# arrayboard_r0.net
KiCad netlist of a schematic drawn in EAGLE
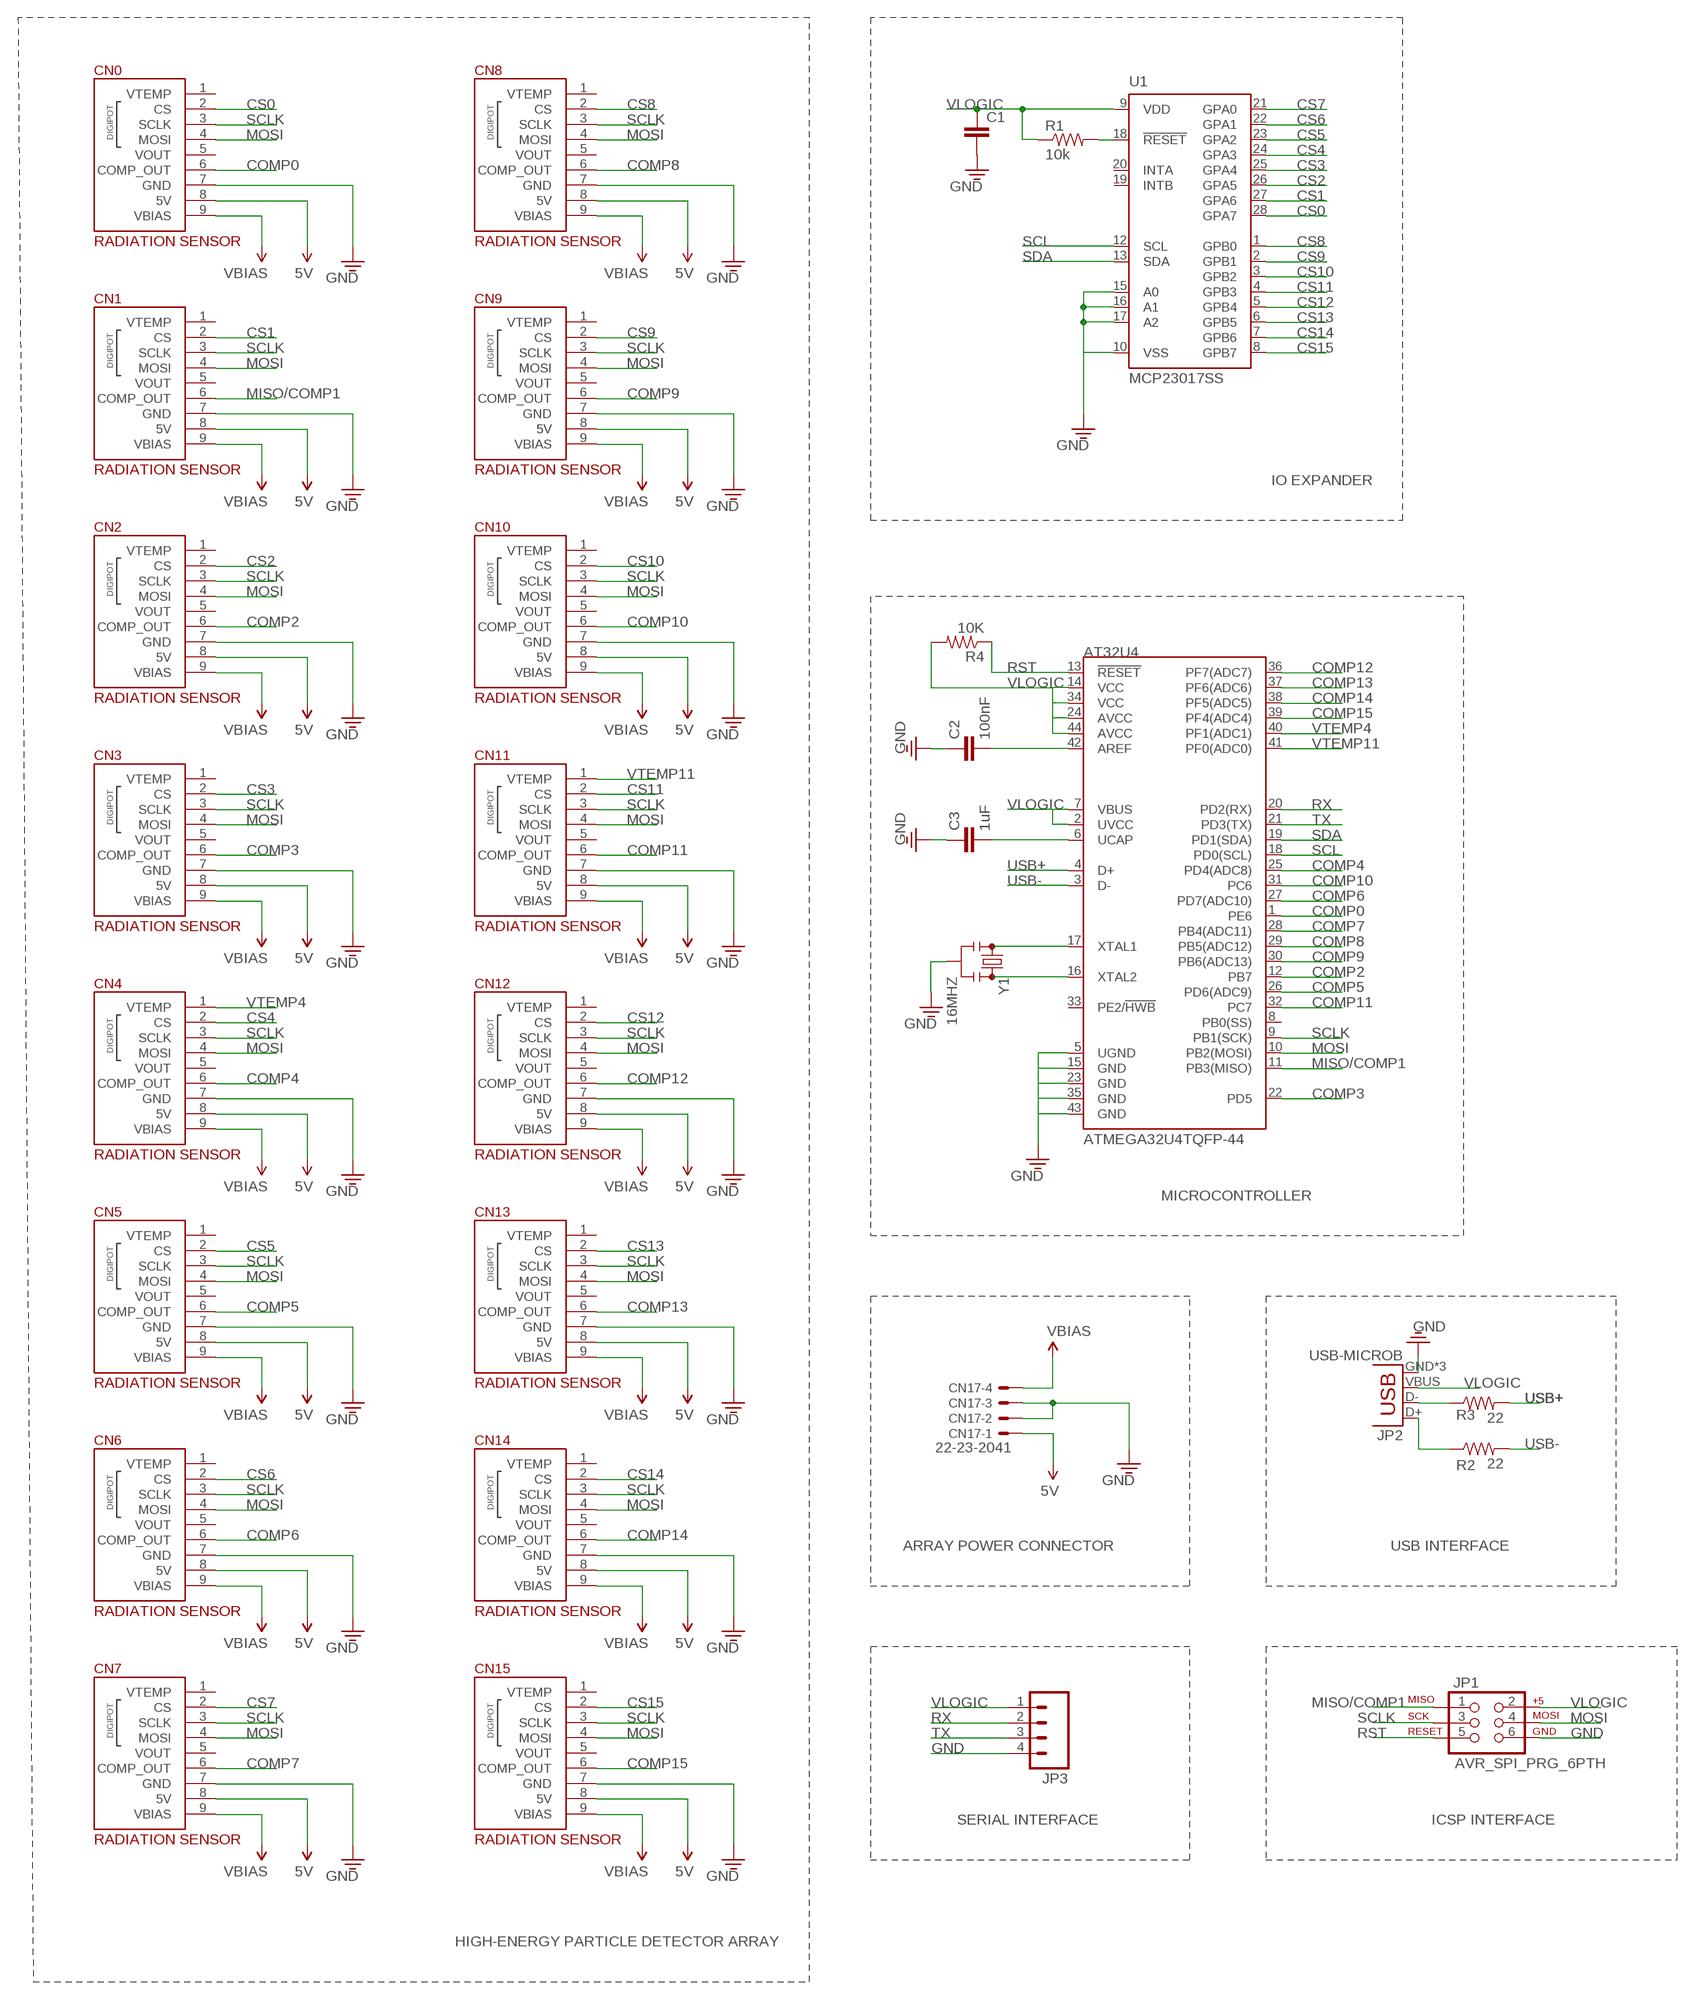
[diagram p0: schematic, sheet 1]

(export (version "E")
  (design (tool "Eeschema 10.0.6"))
  (components
    (comp (ref "AT32U4")
      (value "ATMEGA32U4TQFP-44")
      (footprint "eagle-import:TQFP44")
      (libsource (lib "eagle-import") (part "ATMEGA32U4TQFP-44"))
    )
    (comp (ref "C1")
      (value "CAP0603")
      (footprint "eagle-import:0603")
      (libsource (lib "eagle-import") (part "CAP0603"))
    )
    (comp (ref "C2")
      (value "100nF")
      (footprint "eagle-import:0805")
      (libsource (lib "eagle-import") (part "CAP0805"))
    )
    (comp (ref "C3")
      (value "1uF")
      (footprint "eagle-import:0805")
      (libsource (lib "eagle-import") (part "CAP0805"))
    )
    (comp (ref "CN0")
      (value "RADIATION-SENSOR-REV1")
      (footprint "eagle-import:RADIATION-SENSOR-REV1")
      (libsource (lib "eagle-import") (part "RADIATION-SENSOR-REV1"))
    )
    (comp (ref "CN1")
      (value "RADIATION-SENSOR-REV1")
      (footprint "eagle-import:RADIATION-SENSOR-REV1")
      (libsource (lib "eagle-import") (part "RADIATION-SENSOR-REV1"))
    )
    (comp (ref "CN2")
      (value "RADIATION-SENSOR-REV1")
      (footprint "eagle-import:RADIATION-SENSOR-REV1")
      (libsource (lib "eagle-import") (part "RADIATION-SENSOR-REV1"))
    )
    (comp (ref "CN3")
      (value "RADIATION-SENSOR-REV1")
      (footprint "eagle-import:RADIATION-SENSOR-REV1")
      (libsource (lib "eagle-import") (part "RADIATION-SENSOR-REV1"))
    )
    (comp (ref "CN4")
      (value "RADIATION-SENSOR-REV1")
      (footprint "eagle-import:RADIATION-SENSOR-REV1")
      (libsource (lib "eagle-import") (part "RADIATION-SENSOR-REV1"))
    )
    (comp (ref "CN5")
      (value "RADIATION-SENSOR-REV1")
      (footprint "eagle-import:RADIATION-SENSOR-REV1")
      (libsource (lib "eagle-import") (part "RADIATION-SENSOR-REV1"))
    )
    (comp (ref "CN6")
      (value "RADIATION-SENSOR-REV1")
      (footprint "eagle-import:RADIATION-SENSOR-REV1")
      (libsource (lib "eagle-import") (part "RADIATION-SENSOR-REV1"))
    )
    (comp (ref "CN7")
      (value "RADIATION-SENSOR-REV1")
      (footprint "eagle-import:RADIATION-SENSOR-REV1")
      (libsource (lib "eagle-import") (part "RADIATION-SENSOR-REV1"))
    )
    (comp (ref "CN8")
      (value "RADIATION-SENSOR-REV1")
      (footprint "eagle-import:RADIATION-SENSOR-REV1")
      (libsource (lib "eagle-import") (part "RADIATION-SENSOR-REV1"))
    )
    (comp (ref "CN9")
      (value "RADIATION-SENSOR-REV1")
      (footprint "eagle-import:RADIATION-SENSOR-REV1")
      (libsource (lib "eagle-import") (part "RADIATION-SENSOR-REV1"))
    )
    (comp (ref "CN10")
      (value "RADIATION-SENSOR-REV1")
      (footprint "eagle-import:RADIATION-SENSOR-REV1")
      (libsource (lib "eagle-import") (part "RADIATION-SENSOR-REV1"))
    )
    (comp (ref "CN11")
      (value "RADIATION-SENSOR-REV1")
      (footprint "eagle-import:RADIATION-SENSOR-REV1")
      (libsource (lib "eagle-import") (part "RADIATION-SENSOR-REV1"))
    )
    (comp (ref "CN12")
      (value "RADIATION-SENSOR-REV1")
      (footprint "eagle-import:RADIATION-SENSOR-REV1")
      (libsource (lib "eagle-import") (part "RADIATION-SENSOR-REV1"))
    )
    (comp (ref "CN13")
      (value "RADIATION-SENSOR-REV1")
      (footprint "eagle-import:RADIATION-SENSOR-REV1")
      (libsource (lib "eagle-import") (part "RADIATION-SENSOR-REV1"))
    )
    (comp (ref "CN14")
      (value "RADIATION-SENSOR-REV1")
      (footprint "eagle-import:RADIATION-SENSOR-REV1")
      (libsource (lib "eagle-import") (part "RADIATION-SENSOR-REV1"))
    )
    (comp (ref "CN15")
      (value "RADIATION-SENSOR-REV1")
      (footprint "eagle-import:RADIATION-SENSOR-REV1")
      (libsource (lib "eagle-import") (part "RADIATION-SENSOR-REV1"))
    )
    (comp (ref "CN17")
      (value "22-23-2041")
      (footprint "eagle-import:22-23-2041")
      (fields (field (name "MF") "MOLEX"))
      (libsource (lib "eagle-import") (part "22-23-2041"))
    )
    (comp (ref "JP1")
      (value "AVR_SPI_PRG_6PTH")
      (footprint "eagle-import:2X3")
      (libsource (lib "eagle-import") (part "AVR_SPI_PRG_6PTH"))
    )
    (comp (ref "JP2")
      (value "USB-MICROB")
      (footprint "eagle-import:USB-MICROB")
      (libsource (lib "eagle-import") (part "USB-MICROB"))
    )
    (comp (ref "JP3")
      (value "M04POLAR")
      (footprint "eagle-import:MOLEX-1X4")
      (libsource (lib "eagle-import") (part "M04POLAR"))
    )
    (comp (ref "R1")
      (value "10k")
      (footprint "eagle-import:0603")
      (libsource (lib "eagle-import") (part "RESISTOR0603"))
    )
    (comp (ref "R2")
      (value "22")
      (footprint "eagle-import:0805")
      (libsource (lib "eagle-import") (part "RESISTOR0805-RES"))
    )
    (comp (ref "R3")
      (value "22")
      (footprint "eagle-import:0805")
      (libsource (lib "eagle-import") (part "RESISTOR0805-RES"))
    )
    (comp (ref "R4")
      (value "10K")
      (footprint "eagle-import:0805")
      (libsource (lib "eagle-import") (part "RESISTOR0805-RES"))
    )
    (comp (ref "U1")
      (value "MCP23017SS")
      (footprint "eagle-import:SSOP28")
      (libsource (lib "eagle-import") (part "MCP23017SS"))
    )
    (comp (ref "Y1")
      (value "16MHZ")
      (footprint "eagle-import:RESONATOR-SMD")
      (libsource (lib "eagle-import") (part "RESONATOR16MHZ"))
    )
  )
  (nets
    (net (code "1") (name "/COMP0") (class "Default")
      (node (ref "AT32U4") (pin "1") (pinfunction "PE6_1") (pintype "bidirectional"))
      (node (ref "CN0") (pin "6") (pinfunction "COMP_OUT_6") (pintype "bidirectional"))
    )
    (net (code "2") (name "/COMP2") (class "Default")
      (node (ref "AT32U4") (pin "12") (pinfunction "PB7_12") (pintype "bidirectional"))
      (node (ref "CN2") (pin "6") (pinfunction "COMP_OUT_6") (pintype "bidirectional"))
    )
    (net (code "3") (name "/COMP3") (class "Default")
      (node (ref "AT32U4") (pin "22") (pinfunction "PD5_22") (pintype "bidirectional"))
      (node (ref "CN3") (pin "6") (pinfunction "COMP_OUT_6") (pintype "bidirectional"))
    )
    (net (code "4") (name "/COMP4") (class "Default")
      (node (ref "AT32U4") (pin "25") (pinfunction "PD4(ADC8)_25") (pintype "bidirectional"))
      (node (ref "CN4") (pin "6") (pinfunction "COMP_OUT_6") (pintype "bidirectional"))
    )
    (net (code "5") (name "/COMP5") (class "Default")
      (node (ref "AT32U4") (pin "26") (pinfunction "PD6(ADC9)_26") (pintype "bidirectional"))
      (node (ref "CN5") (pin "6") (pinfunction "COMP_OUT_6") (pintype "bidirectional"))
    )
    (net (code "6") (name "/COMP6") (class "Default")
      (node (ref "AT32U4") (pin "27") (pinfunction "PD7(ADC10)_27") (pintype "bidirectional"))
      (node (ref "CN6") (pin "6") (pinfunction "COMP_OUT_6") (pintype "bidirectional"))
    )
    (net (code "7") (name "/COMP7") (class "Default")
      (node (ref "AT32U4") (pin "28") (pinfunction "PB4(ADC11)_28") (pintype "bidirectional"))
      (node (ref "CN7") (pin "6") (pinfunction "COMP_OUT_6") (pintype "bidirectional"))
    )
    (net (code "8") (name "/COMP8") (class "Default")
      (node (ref "AT32U4") (pin "29") (pinfunction "PB5(ADC12)_29") (pintype "bidirectional"))
      (node (ref "CN8") (pin "6") (pinfunction "COMP_OUT_6") (pintype "bidirectional"))
    )
    (net (code "9") (name "/COMP9") (class "Default")
      (node (ref "AT32U4") (pin "30") (pinfunction "PB6(ADC13)_30") (pintype "bidirectional"))
      (node (ref "CN9") (pin "6") (pinfunction "COMP_OUT_6") (pintype "bidirectional"))
    )
    (net (code "10") (name "/COMP10") (class "Default")
      (node (ref "AT32U4") (pin "31") (pinfunction "PC6_31") (pintype "bidirectional"))
      (node (ref "CN10") (pin "6") (pinfunction "COMP_OUT_6") (pintype "bidirectional"))
    )
    (net (code "11") (name "/COMP11") (class "Default")
      (node (ref "AT32U4") (pin "32") (pinfunction "PC7_32") (pintype "bidirectional"))
      (node (ref "CN11") (pin "6") (pinfunction "COMP_OUT_6") (pintype "bidirectional"))
    )
    (net (code "12") (name "/COMP12") (class "Default")
      (node (ref "AT32U4") (pin "36") (pinfunction "PF7(ADC7)_36") (pintype "bidirectional"))
      (node (ref "CN12") (pin "6") (pinfunction "COMP_OUT_6") (pintype "bidirectional"))
    )
    (net (code "13") (name "/COMP13") (class "Default")
      (node (ref "AT32U4") (pin "37") (pinfunction "PF6(ADC6)_37") (pintype "bidirectional"))
      (node (ref "CN13") (pin "6") (pinfunction "COMP_OUT_6") (pintype "bidirectional"))
    )
    (net (code "14") (name "/COMP14") (class "Default")
      (node (ref "AT32U4") (pin "38") (pinfunction "PF5(ADC5)_38") (pintype "bidirectional"))
      (node (ref "CN14") (pin "6") (pinfunction "COMP_OUT_6") (pintype "bidirectional"))
    )
    (net (code "15") (name "/COMP15") (class "Default")
      (node (ref "AT32U4") (pin "39") (pinfunction "PF4(ADC4)_39") (pintype "bidirectional"))
      (node (ref "CN15") (pin "6") (pinfunction "COMP_OUT_6") (pintype "bidirectional"))
    )
    (net (code "16") (name "/CS0") (class "Default")
      (node (ref "CN0") (pin "2") (pinfunction "CS_2") (pintype "bidirectional"))
      (node (ref "U1") (pin "28") (pinfunction "GPA7_28") (pintype "bidirectional"))
    )
    (net (code "17") (name "/CS1") (class "Default")
      (node (ref "CN1") (pin "2") (pinfunction "CS_2") (pintype "bidirectional"))
      (node (ref "U1") (pin "27") (pinfunction "GPA6_27") (pintype "bidirectional"))
    )
    (net (code "18") (name "/CS2") (class "Default")
      (node (ref "CN2") (pin "2") (pinfunction "CS_2") (pintype "bidirectional"))
      (node (ref "U1") (pin "26") (pinfunction "GPA5_26") (pintype "bidirectional"))
    )
    (net (code "19") (name "/CS3") (class "Default")
      (node (ref "CN3") (pin "2") (pinfunction "CS_2") (pintype "bidirectional"))
      (node (ref "U1") (pin "25") (pinfunction "GPA4_25") (pintype "bidirectional"))
    )
    (net (code "20") (name "/CS4") (class "Default")
      (node (ref "CN4") (pin "2") (pinfunction "CS_2") (pintype "bidirectional"))
      (node (ref "U1") (pin "24") (pinfunction "GPA3_24") (pintype "bidirectional"))
    )
    (net (code "21") (name "/CS5") (class "Default")
      (node (ref "CN5") (pin "2") (pinfunction "CS_2") (pintype "bidirectional"))
      (node (ref "U1") (pin "23") (pinfunction "GPA2_23") (pintype "bidirectional"))
    )
    (net (code "22") (name "/CS6") (class "Default")
      (node (ref "CN6") (pin "2") (pinfunction "CS_2") (pintype "bidirectional"))
      (node (ref "U1") (pin "22") (pinfunction "GPA1_22") (pintype "bidirectional"))
    )
    (net (code "23") (name "/CS7") (class "Default")
      (node (ref "CN7") (pin "2") (pinfunction "CS_2") (pintype "bidirectional"))
      (node (ref "U1") (pin "21") (pinfunction "GPA0_21") (pintype "bidirectional"))
    )
    (net (code "24") (name "/CS8") (class "Default")
      (node (ref "CN8") (pin "2") (pinfunction "CS_2") (pintype "bidirectional"))
      (node (ref "U1") (pin "1") (pinfunction "GPB0_1") (pintype "bidirectional"))
    )
    (net (code "25") (name "/CS9") (class "Default")
      (node (ref "CN9") (pin "2") (pinfunction "CS_2") (pintype "bidirectional"))
      (node (ref "U1") (pin "2") (pinfunction "GPB1_2") (pintype "bidirectional"))
    )
    (net (code "26") (name "/CS10") (class "Default")
      (node (ref "CN10") (pin "2") (pinfunction "CS_2") (pintype "bidirectional"))
      (node (ref "U1") (pin "3") (pinfunction "GPB2_3") (pintype "bidirectional"))
    )
    (net (code "27") (name "/CS11") (class "Default")
      (node (ref "CN11") (pin "2") (pinfunction "CS_2") (pintype "bidirectional"))
      (node (ref "U1") (pin "4") (pinfunction "GPB3_4") (pintype "bidirectional"))
    )
    (net (code "28") (name "/CS12") (class "Default")
      (node (ref "CN12") (pin "2") (pinfunction "CS_2") (pintype "bidirectional"))
      (node (ref "U1") (pin "5") (pinfunction "GPB4_5") (pintype "bidirectional"))
    )
    (net (code "29") (name "/CS13") (class "Default")
      (node (ref "CN13") (pin "2") (pinfunction "CS_2") (pintype "bidirectional"))
      (node (ref "U1") (pin "6") (pinfunction "GPB5_6") (pintype "bidirectional"))
    )
    (net (code "30") (name "/CS14") (class "Default")
      (node (ref "CN14") (pin "2") (pinfunction "CS_2") (pintype "bidirectional"))
      (node (ref "U1") (pin "7") (pinfunction "GPB6_7") (pintype "bidirectional"))
    )
    (net (code "31") (name "/CS15") (class "Default")
      (node (ref "CN15") (pin "2") (pinfunction "CS_2") (pintype "bidirectional"))
      (node (ref "U1") (pin "8") (pinfunction "GPB7_8") (pintype "bidirectional"))
    )
    (net (code "32") (name "/MISO{slash}COMP1") (class "Default")
      (node (ref "AT32U4") (pin "11") (pinfunction "PB3(MISO)_11") (pintype "bidirectional"))
      (node (ref "CN1") (pin "6") (pinfunction "COMP_OUT_6") (pintype "bidirectional"))
      (node (ref "JP1") (pin "1") (pinfunction "1_1") (pintype "passive"))
    )
    (net (code "33") (name "/MOSI") (class "Default")
      (node (ref "AT32U4") (pin "10") (pinfunction "PB2(MOSI)_10") (pintype "bidirectional"))
      (node (ref "CN0") (pin "4") (pinfunction "MOSI_4") (pintype "bidirectional"))
      (node (ref "CN1") (pin "4") (pinfunction "MOSI_4") (pintype "bidirectional"))
      (node (ref "CN10") (pin "4") (pinfunction "MOSI_4") (pintype "bidirectional"))
      (node (ref "CN11") (pin "4") (pinfunction "MOSI_4") (pintype "bidirectional"))
      (node (ref "CN12") (pin "4") (pinfunction "MOSI_4") (pintype "bidirectional"))
      (node (ref "CN13") (pin "4") (pinfunction "MOSI_4") (pintype "bidirectional"))
      (node (ref "CN14") (pin "4") (pinfunction "MOSI_4") (pintype "bidirectional"))
      (node (ref "CN15") (pin "4") (pinfunction "MOSI_4") (pintype "bidirectional"))
      (node (ref "CN2") (pin "4") (pinfunction "MOSI_4") (pintype "bidirectional"))
      (node (ref "CN3") (pin "4") (pinfunction "MOSI_4") (pintype "bidirectional"))
      (node (ref "CN4") (pin "4") (pinfunction "MOSI_4") (pintype "bidirectional"))
      (node (ref "CN5") (pin "4") (pinfunction "MOSI_4") (pintype "bidirectional"))
      (node (ref "CN6") (pin "4") (pinfunction "MOSI_4") (pintype "bidirectional"))
      (node (ref "CN7") (pin "4") (pinfunction "MOSI_4") (pintype "bidirectional"))
      (node (ref "CN8") (pin "4") (pinfunction "MOSI_4") (pintype "bidirectional"))
      (node (ref "CN9") (pin "4") (pinfunction "MOSI_4") (pintype "bidirectional"))
      (node (ref "JP1") (pin "4") (pinfunction "4_4") (pintype "passive"))
    )
    (net (code "34") (name "/RST") (class "Default")
      (node (ref "AT32U4") (pin "13") (pinfunction "~{RESET}_13") (pintype "bidirectional"))
      (node (ref "JP1") (pin "5") (pinfunction "5_5") (pintype "passive"))
      (node (ref "R4") (pin "1") (pinfunction "1_1") (pintype "passive"))
    )
    (net (code "35") (name "/RX") (class "Default")
      (node (ref "AT32U4") (pin "20") (pinfunction "PD2(RX)_20") (pintype "bidirectional"))
      (node (ref "JP3") (pin "2") (pinfunction "2_2") (pintype "passive"))
    )
    (net (code "36") (name "/SCL") (class "Default")
      (node (ref "AT32U4") (pin "18") (pinfunction "PD0(SCL)_18") (pintype "bidirectional"))
      (node (ref "U1") (pin "12") (pinfunction "SCL_12") (pintype "input"))
    )
    (net (code "37") (name "/SCLK") (class "Default")
      (node (ref "AT32U4") (pin "9") (pinfunction "PB1(SCK)_9") (pintype "bidirectional"))
      (node (ref "CN0") (pin "3") (pinfunction "SCLK_3") (pintype "bidirectional"))
      (node (ref "CN1") (pin "3") (pinfunction "SCLK_3") (pintype "bidirectional"))
      (node (ref "CN10") (pin "3") (pinfunction "SCLK_3") (pintype "bidirectional"))
      (node (ref "CN11") (pin "3") (pinfunction "SCLK_3") (pintype "bidirectional"))
      (node (ref "CN12") (pin "3") (pinfunction "SCLK_3") (pintype "bidirectional"))
      (node (ref "CN13") (pin "3") (pinfunction "SCLK_3") (pintype "bidirectional"))
      (node (ref "CN14") (pin "3") (pinfunction "SCLK_3") (pintype "bidirectional"))
      (node (ref "CN15") (pin "3") (pinfunction "SCLK_3") (pintype "bidirectional"))
      (node (ref "CN2") (pin "3") (pinfunction "SCLK_3") (pintype "bidirectional"))
      (node (ref "CN3") (pin "3") (pinfunction "SCLK_3") (pintype "bidirectional"))
      (node (ref "CN4") (pin "3") (pinfunction "SCLK_3") (pintype "bidirectional"))
      (node (ref "CN5") (pin "3") (pinfunction "SCLK_3") (pintype "bidirectional"))
      (node (ref "CN6") (pin "3") (pinfunction "SCLK_3") (pintype "bidirectional"))
      (node (ref "CN7") (pin "3") (pinfunction "SCLK_3") (pintype "bidirectional"))
      (node (ref "CN8") (pin "3") (pinfunction "SCLK_3") (pintype "bidirectional"))
      (node (ref "CN9") (pin "3") (pinfunction "SCLK_3") (pintype "bidirectional"))
      (node (ref "JP1") (pin "3") (pinfunction "3_3") (pintype "passive"))
    )
    (net (code "38") (name "/SDA") (class "Default")
      (node (ref "AT32U4") (pin "19") (pinfunction "PD1(SDA)_19") (pintype "bidirectional"))
      (node (ref "U1") (pin "13") (pinfunction "SDA_13") (pintype "bidirectional"))
    )
    (net (code "39") (name "/TX") (class "Default")
      (node (ref "AT32U4") (pin "21") (pinfunction "PD3(TX)_21") (pintype "bidirectional"))
      (node (ref "JP3") (pin "3") (pinfunction "3_3") (pintype "passive"))
    )
    (net (code "40") (name "/USB+") (class "Default")
      (node (ref "AT32U4") (pin "4") (pinfunction "D+_4") (pintype "bidirectional"))
      (node (ref "R3") (pin "2") (pinfunction "2_2") (pintype "passive"))
    )
    (net (code "41") (name "/USB-") (class "Default")
      (node (ref "AT32U4") (pin "3") (pinfunction "D-_3") (pintype "bidirectional"))
      (node (ref "R2") (pin "2") (pinfunction "2_2") (pintype "passive"))
    )
    (net (code "42") (name "/VLOGIC") (class "Default")
      (node (ref "AT32U4") (pin "14") (pinfunction "VCC_14") (pintype "bidirectional"))
      (node (ref "AT32U4") (pin "24") (pinfunction "AVCC_24") (pintype "bidirectional"))
      (node (ref "AT32U4") (pin "34") (pinfunction "VCC_34") (pintype "bidirectional"))
      (node (ref "AT32U4") (pin "44") (pinfunction "AVCC_44") (pintype "bidirectional"))
      (node (ref "AT32U4") (pin "7") (pinfunction "VBUS_7") (pintype "bidirectional"))
      (node (ref "C1") (pin "1") (pinfunction "1_1") (pintype "passive"))
      (node (ref "JP1") (pin "2") (pinfunction "2_2") (pintype "passive"))
      (node (ref "JP2") (pin "VBUS") (pinfunction "VBUS_VBUS") (pintype "bidirectional"))
      (node (ref "JP3") (pin "1") (pinfunction "1_1") (pintype "passive"))
      (node (ref "R1") (pin "1") (pinfunction "1_1") (pintype "passive"))
      (node (ref "R4") (pin "2") (pinfunction "2_2") (pintype "passive"))
      (node (ref "U1") (pin "9") (pinfunction "VDD_9") (pintype "power_in"))
    )
    (net (code "43") (name "/VTEMP4") (class "Default")
      (node (ref "AT32U4") (pin "40") (pinfunction "PF1(ADC1)_40") (pintype "bidirectional"))
      (node (ref "CN4") (pin "1") (pinfunction "VTEMP_1") (pintype "bidirectional"))
    )
    (net (code "44") (name "/VTEMP11") (class "Default")
      (node (ref "AT32U4") (pin "41") (pinfunction "PF0(ADC0)_41") (pintype "bidirectional"))
      (node (ref "CN11") (pin "1") (pinfunction "VTEMP_1") (pintype "bidirectional"))
    )
    (net (code "45") (name "5V") (class "Default")
      (node (ref "CN0") (pin "8") (pinfunction "5V_8") (pintype "bidirectional"))
      (node (ref "CN1") (pin "8") (pinfunction "5V_8") (pintype "bidirectional"))
      (node (ref "CN10") (pin "8") (pinfunction "5V_8") (pintype "bidirectional"))
      (node (ref "CN11") (pin "8") (pinfunction "5V_8") (pintype "bidirectional"))
      (node (ref "CN12") (pin "8") (pinfunction "5V_8") (pintype "bidirectional"))
      (node (ref "CN13") (pin "8") (pinfunction "5V_8") (pintype "bidirectional"))
      (node (ref "CN14") (pin "8") (pinfunction "5V_8") (pintype "bidirectional"))
      (node (ref "CN15") (pin "8") (pinfunction "5V_8") (pintype "bidirectional"))
      (node (ref "CN17") (pin "1") (pinfunction "S_1") (pintype "passive"))
      (node (ref "CN2") (pin "8") (pinfunction "5V_8") (pintype "bidirectional"))
      (node (ref "CN3") (pin "8") (pinfunction "5V_8") (pintype "bidirectional"))
      (node (ref "CN4") (pin "8") (pinfunction "5V_8") (pintype "bidirectional"))
      (node (ref "CN5") (pin "8") (pinfunction "5V_8") (pintype "bidirectional"))
      (node (ref "CN6") (pin "8") (pinfunction "5V_8") (pintype "bidirectional"))
      (node (ref "CN7") (pin "8") (pinfunction "5V_8") (pintype "bidirectional"))
      (node (ref "CN8") (pin "8") (pinfunction "5V_8") (pintype "bidirectional"))
      (node (ref "CN9") (pin "8") (pinfunction "5V_8") (pintype "bidirectional"))
    )
    (net (code "46") (name "GND") (class "Default")
      (node (ref "AT32U4") (pin "15") (pinfunction "GND_15") (pintype "bidirectional"))
      (node (ref "AT32U4") (pin "23") (pinfunction "GND_23") (pintype "bidirectional"))
      (node (ref "AT32U4") (pin "35") (pinfunction "GND_35") (pintype "bidirectional"))
      (node (ref "AT32U4") (pin "43") (pinfunction "GND_43") (pintype "bidirectional"))
      (node (ref "AT32U4") (pin "5") (pinfunction "UGND_5") (pintype "bidirectional"))
      (node (ref "C1") (pin "2") (pinfunction "2_2") (pintype "passive"))
      (node (ref "C2") (pin "1") (pinfunction "1_1") (pintype "passive"))
      (node (ref "C3") (pin "1") (pinfunction "1_1") (pintype "passive"))
      (node (ref "CN0") (pin "7") (pinfunction "GND_7") (pintype "bidirectional"))
      (node (ref "CN1") (pin "7") (pinfunction "GND_7") (pintype "bidirectional"))
      (node (ref "CN10") (pin "7") (pinfunction "GND_7") (pintype "bidirectional"))
      (node (ref "CN11") (pin "7") (pinfunction "GND_7") (pintype "bidirectional"))
      (node (ref "CN12") (pin "7") (pinfunction "GND_7") (pintype "bidirectional"))
      (node (ref "CN13") (pin "7") (pinfunction "GND_7") (pintype "bidirectional"))
      (node (ref "CN14") (pin "7") (pinfunction "GND_7") (pintype "bidirectional"))
      (node (ref "CN15") (pin "7") (pinfunction "GND_7") (pintype "bidirectional"))
      (node (ref "CN17") (pin "2") (pinfunction "S_2") (pintype "passive"))
      (node (ref "CN17") (pin "3") (pinfunction "S_3") (pintype "passive"))
      (node (ref "CN2") (pin "7") (pinfunction "GND_7") (pintype "bidirectional"))
      (node (ref "CN3") (pin "7") (pinfunction "GND_7") (pintype "bidirectional"))
      (node (ref "CN4") (pin "7") (pinfunction "GND_7") (pintype "bidirectional"))
      (node (ref "CN5") (pin "7") (pinfunction "GND_7") (pintype "bidirectional"))
      (node (ref "CN6") (pin "7") (pinfunction "GND_7") (pintype "bidirectional"))
      (node (ref "CN7") (pin "7") (pinfunction "GND_7") (pintype "bidirectional"))
      (node (ref "CN8") (pin "7") (pinfunction "GND_7") (pintype "bidirectional"))
      (node (ref "CN9") (pin "7") (pinfunction "GND_7") (pintype "bidirectional"))
      (node (ref "JP1") (pin "6") (pinfunction "6_6") (pintype "passive"))
      (node (ref "JP2") (pin "GND") (pinfunction "GND_GND") (pintype "bidirectional"))
      (node (ref "JP2") (pin "MT1") (pinfunction "GND_MT1") (pintype "bidirectional"))
      (node (ref "JP2") (pin "MT2") (pinfunction "GND_MT2") (pintype "bidirectional"))
      (node (ref "JP3") (pin "4") (pinfunction "4_4") (pintype "passive"))
      (node (ref "U1") (pin "10") (pinfunction "VSS_10") (pintype "power_in"))
      (node (ref "U1") (pin "15") (pinfunction "A0_15") (pintype "input"))
      (node (ref "U1") (pin "16") (pinfunction "A1_16") (pintype "input"))
      (node (ref "U1") (pin "17") (pinfunction "A2_17") (pintype "input"))
      (node (ref "Y1") (pin "2") (pinfunction "2_2") (pintype "passive"))
    )
    (net (code "47") (name "Net-(AT32U4-AREF)") (class "Default")
      (node (ref "AT32U4") (pin "42") (pinfunction "AREF_42") (pintype "bidirectional"))
      (node (ref "C2") (pin "2") (pinfunction "2_2") (pintype "passive"))
    )
    (net (code "48") (name "Net-(AT32U4-UCAP)") (class "Default")
      (node (ref "AT32U4") (pin "6") (pinfunction "UCAP_6") (pintype "bidirectional"))
      (node (ref "C3") (pin "2") (pinfunction "2_2") (pintype "passive"))
    )
    (net (code "49") (name "Net-(AT32U4-XTAL1)") (class "Default")
      (node (ref "AT32U4") (pin "17") (pinfunction "XTAL1_17") (pintype "bidirectional"))
      (node (ref "Y1") (pin "1") (pinfunction "1_1") (pintype "passive"))
    )
    (net (code "50") (name "Net-(AT32U4-XTAL2)") (class "Default")
      (node (ref "AT32U4") (pin "16") (pinfunction "XTAL2_16") (pintype "bidirectional"))
      (node (ref "Y1") (pin "3") (pinfunction "3_3") (pintype "passive"))
    )
    (net (code "51") (name "Net-(JP2-PadD+)") (class "Default")
      (node (ref "JP2") (pin "D+") (pinfunction "D+_D+") (pintype "bidirectional"))
      (node (ref "R2") (pin "1") (pinfunction "1_1") (pintype "passive"))
    )
    (net (code "52") (name "Net-(JP2-PadD-)") (class "Default")
      (node (ref "JP2") (pin "D-") (pinfunction "D-_D-") (pintype "bidirectional"))
      (node (ref "R3") (pin "1") (pinfunction "1_1") (pintype "passive"))
    )
    (net (code "53") (name "Net-(U1-~{RESET})") (class "Default")
      (node (ref "R1") (pin "2") (pinfunction "2_2") (pintype "passive"))
      (node (ref "U1") (pin "18") (pinfunction "~{RESET}_18") (pintype "input"))
    )
    (net (code "54") (name "VBIAS") (class "Default")
      (node (ref "CN0") (pin "9") (pinfunction "VBIAS_9") (pintype "bidirectional"))
      (node (ref "CN1") (pin "9") (pinfunction "VBIAS_9") (pintype "bidirectional"))
      (node (ref "CN10") (pin "9") (pinfunction "VBIAS_9") (pintype "bidirectional"))
      (node (ref "CN11") (pin "9") (pinfunction "VBIAS_9") (pintype "bidirectional"))
      (node (ref "CN12") (pin "9") (pinfunction "VBIAS_9") (pintype "bidirectional"))
      (node (ref "CN13") (pin "9") (pinfunction "VBIAS_9") (pintype "bidirectional"))
      (node (ref "CN14") (pin "9") (pinfunction "VBIAS_9") (pintype "bidirectional"))
      (node (ref "CN15") (pin "9") (pinfunction "VBIAS_9") (pintype "bidirectional"))
      (node (ref "CN17") (pin "4") (pinfunction "S_4") (pintype "passive"))
      (node (ref "CN2") (pin "9") (pinfunction "VBIAS_9") (pintype "bidirectional"))
      (node (ref "CN3") (pin "9") (pinfunction "VBIAS_9") (pintype "bidirectional"))
      (node (ref "CN4") (pin "9") (pinfunction "VBIAS_9") (pintype "bidirectional"))
      (node (ref "CN5") (pin "9") (pinfunction "VBIAS_9") (pintype "bidirectional"))
      (node (ref "CN6") (pin "9") (pinfunction "VBIAS_9") (pintype "bidirectional"))
      (node (ref "CN7") (pin "9") (pinfunction "VBIAS_9") (pintype "bidirectional"))
      (node (ref "CN8") (pin "9") (pinfunction "VBIAS_9") (pintype "bidirectional"))
      (node (ref "CN9") (pin "9") (pinfunction "VBIAS_9") (pintype "bidirectional"))
    )
    (net (code "55") (name "unconnected-(AT32U4-PB0(SS)-Pad8)") (class "Default")
      (node (ref "AT32U4") (pin "8") (pinfunction "PB0(SS)_8") (pintype "bidirectional"))
    )
    (net (code "56") (name "unconnected-(AT32U4-PE2{slash}~{HWB}-Pad33)") (class "Default")
      (node (ref "AT32U4") (pin "33") (pinfunction "PE2/~{HWB}_33") (pintype "bidirectional"))
    )
    (net (code "57") (name "unconnected-(AT32U4-UVCC-Pad2)") (class "Default")
      (node (ref "AT32U4") (pin "2") (pinfunction "UVCC_2") (pintype "bidirectional"))
    )
    (net (code "58") (name "unconnected-(CN0-VOUT-Pad5)") (class "Default")
      (node (ref "CN0") (pin "5") (pinfunction "VOUT_5") (pintype "bidirectional"))
    )
    (net (code "59") (name "unconnected-(CN0-VTEMP-Pad1)") (class "Default")
      (node (ref "CN0") (pin "1") (pinfunction "VTEMP_1") (pintype "bidirectional"))
    )
    (net (code "60") (name "unconnected-(CN1-VOUT-Pad5)") (class "Default")
      (node (ref "CN1") (pin "5") (pinfunction "VOUT_5") (pintype "bidirectional"))
    )
    (net (code "61") (name "unconnected-(CN1-VTEMP-Pad1)") (class "Default")
      (node (ref "CN1") (pin "1") (pinfunction "VTEMP_1") (pintype "bidirectional"))
    )
    (net (code "62") (name "unconnected-(CN2-VOUT-Pad5)") (class "Default")
      (node (ref "CN2") (pin "5") (pinfunction "VOUT_5") (pintype "bidirectional"))
    )
    (net (code "63") (name "unconnected-(CN2-VTEMP-Pad1)") (class "Default")
      (node (ref "CN2") (pin "1") (pinfunction "VTEMP_1") (pintype "bidirectional"))
    )
    (net (code "64") (name "unconnected-(CN3-VOUT-Pad5)") (class "Default")
      (node (ref "CN3") (pin "5") (pinfunction "VOUT_5") (pintype "bidirectional"))
    )
    (net (code "65") (name "unconnected-(CN3-VTEMP-Pad1)") (class "Default")
      (node (ref "CN3") (pin "1") (pinfunction "VTEMP_1") (pintype "bidirectional"))
    )
    (net (code "66") (name "unconnected-(CN4-VOUT-Pad5)") (class "Default")
      (node (ref "CN4") (pin "5") (pinfunction "VOUT_5") (pintype "bidirectional"))
    )
    (net (code "67") (name "unconnected-(CN5-VOUT-Pad5)") (class "Default")
      (node (ref "CN5") (pin "5") (pinfunction "VOUT_5") (pintype "bidirectional"))
    )
    (net (code "68") (name "unconnected-(CN5-VTEMP-Pad1)") (class "Default")
      (node (ref "CN5") (pin "1") (pinfunction "VTEMP_1") (pintype "bidirectional"))
    )
    (net (code "69") (name "unconnected-(CN6-VOUT-Pad5)") (class "Default")
      (node (ref "CN6") (pin "5") (pinfunction "VOUT_5") (pintype "bidirectional"))
    )
    (net (code "70") (name "unconnected-(CN6-VTEMP-Pad1)") (class "Default")
      (node (ref "CN6") (pin "1") (pinfunction "VTEMP_1") (pintype "bidirectional"))
    )
    (net (code "71") (name "unconnected-(CN7-VOUT-Pad5)") (class "Default")
      (node (ref "CN7") (pin "5") (pinfunction "VOUT_5") (pintype "bidirectional"))
    )
    (net (code "72") (name "unconnected-(CN7-VTEMP-Pad1)") (class "Default")
      (node (ref "CN7") (pin "1") (pinfunction "VTEMP_1") (pintype "bidirectional"))
    )
    (net (code "73") (name "unconnected-(CN8-VOUT-Pad5)") (class "Default")
      (node (ref "CN8") (pin "5") (pinfunction "VOUT_5") (pintype "bidirectional"))
    )
    (net (code "74") (name "unconnected-(CN8-VTEMP-Pad1)") (class "Default")
      (node (ref "CN8") (pin "1") (pinfunction "VTEMP_1") (pintype "bidirectional"))
    )
    (net (code "75") (name "unconnected-(CN9-VOUT-Pad5)") (class "Default")
      (node (ref "CN9") (pin "5") (pinfunction "VOUT_5") (pintype "bidirectional"))
    )
    (net (code "76") (name "unconnected-(CN9-VTEMP-Pad1)") (class "Default")
      (node (ref "CN9") (pin "1") (pinfunction "VTEMP_1") (pintype "bidirectional"))
    )
    (net (code "77") (name "unconnected-(CN10-VOUT-Pad5)") (class "Default")
      (node (ref "CN10") (pin "5") (pinfunction "VOUT_5") (pintype "bidirectional"))
    )
    (net (code "78") (name "unconnected-(CN10-VTEMP-Pad1)") (class "Default")
      (node (ref "CN10") (pin "1") (pinfunction "VTEMP_1") (pintype "bidirectional"))
    )
    (net (code "79") (name "unconnected-(CN11-VOUT-Pad5)") (class "Default")
      (node (ref "CN11") (pin "5") (pinfunction "VOUT_5") (pintype "bidirectional"))
    )
    (net (code "80") (name "unconnected-(CN12-VOUT-Pad5)") (class "Default")
      (node (ref "CN12") (pin "5") (pinfunction "VOUT_5") (pintype "bidirectional"))
    )
    (net (code "81") (name "unconnected-(CN12-VTEMP-Pad1)") (class "Default")
      (node (ref "CN12") (pin "1") (pinfunction "VTEMP_1") (pintype "bidirectional"))
    )
    (net (code "82") (name "unconnected-(CN13-VOUT-Pad5)") (class "Default")
      (node (ref "CN13") (pin "5") (pinfunction "VOUT_5") (pintype "bidirectional"))
    )
    (net (code "83") (name "unconnected-(CN13-VTEMP-Pad1)") (class "Default")
      (node (ref "CN13") (pin "1") (pinfunction "VTEMP_1") (pintype "bidirectional"))
    )
    (net (code "84") (name "unconnected-(CN14-VOUT-Pad5)") (class "Default")
      (node (ref "CN14") (pin "5") (pinfunction "VOUT_5") (pintype "bidirectional"))
    )
    (net (code "85") (name "unconnected-(CN14-VTEMP-Pad1)") (class "Default")
      (node (ref "CN14") (pin "1") (pinfunction "VTEMP_1") (pintype "bidirectional"))
    )
    (net (code "86") (name "unconnected-(CN15-VOUT-Pad5)") (class "Default")
      (node (ref "CN15") (pin "5") (pinfunction "VOUT_5") (pintype "bidirectional"))
    )
    (net (code "87") (name "unconnected-(CN15-VTEMP-Pad1)") (class "Default")
      (node (ref "CN15") (pin "1") (pinfunction "VTEMP_1") (pintype "bidirectional"))
    )
    (net (code "88") (name "unconnected-(U1-INTA-Pad20)") (class "Default")
      (node (ref "U1") (pin "20") (pinfunction "INTA_20") (pintype "output"))
    )
    (net (code "89") (name "unconnected-(U1-INTB-Pad19)") (class "Default")
      (node (ref "U1") (pin "19") (pinfunction "INTB_19") (pintype "output"))
    )
  )
)
